# STM8S_RF433_RELAY_LEARN_CODE_V1.net
KiCad netlist of a schematic drawn in Altium Designer
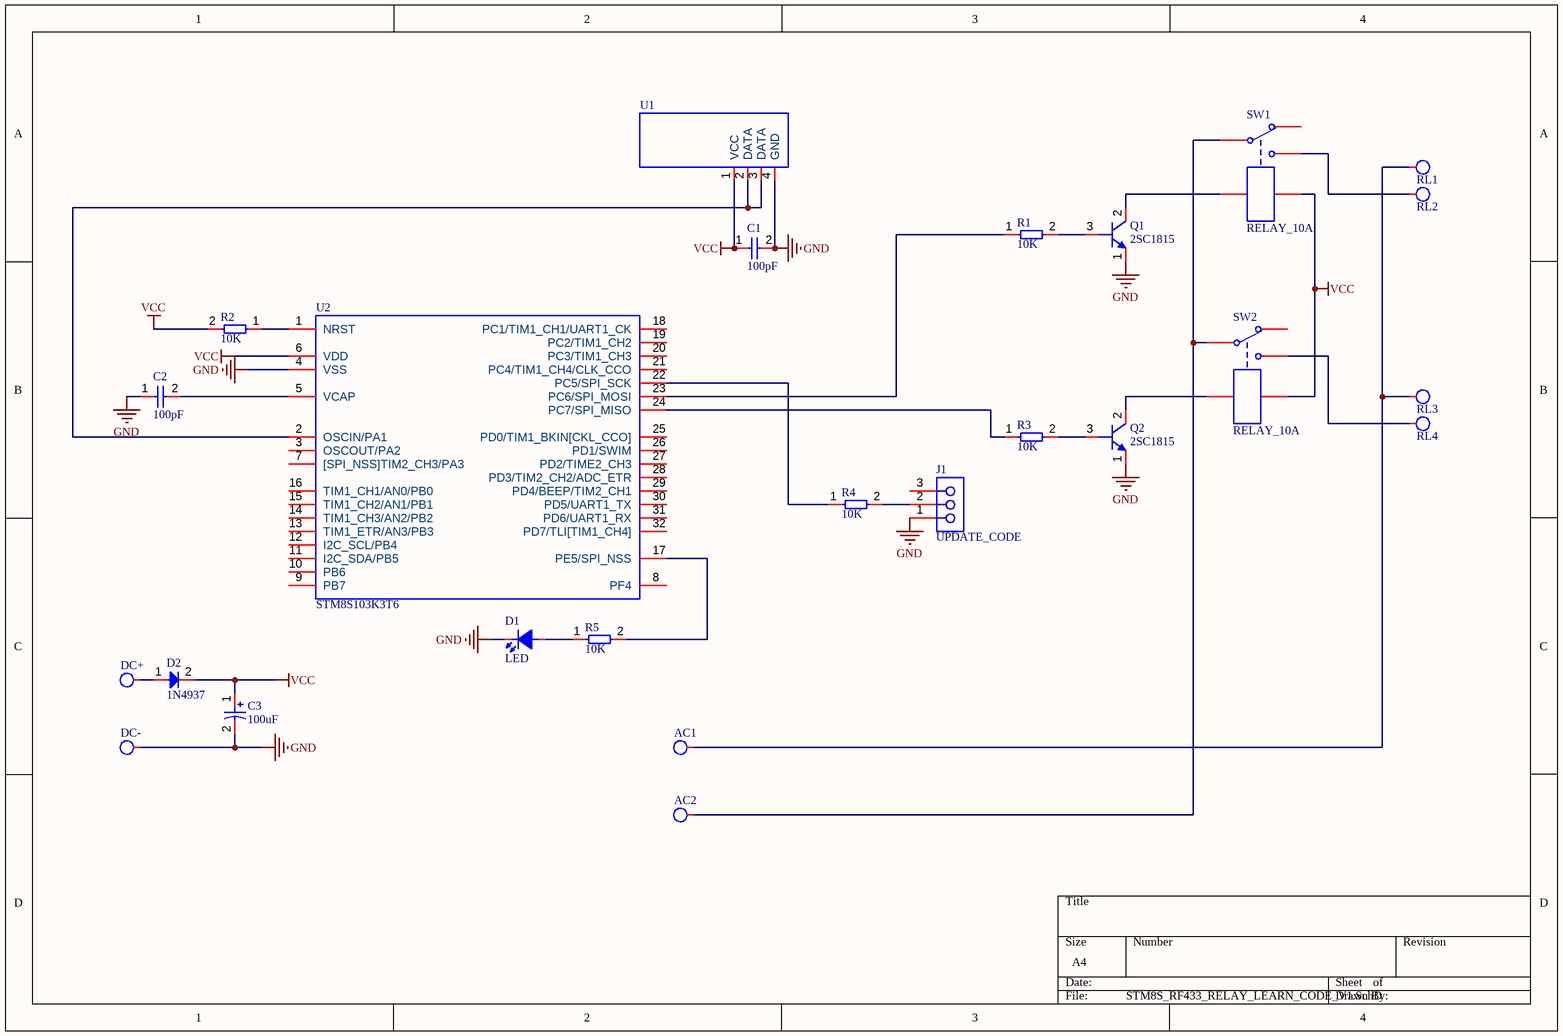
[diagram p0: STM8S_RF433_RELAY_LEARN_CODE_V1.SchDoc]

(export (version "E")
  (design (tool "Eeschema 10.0.6"))
  (components
    (comp (ref "AC1")
      (value "SolderPoint")
      (footprint "SolderPoint")
      (libsource (lib "Lib31082020") (part "SolderPoint"))
    )
    (comp (ref "AC2")
      (value "SolderPoint")
      (footprint "SolderPoint")
      (libsource (lib "Lib31082020") (part "SolderPoint"))
    )
    (comp (ref "C1")
      (value "100pF")
      (footprint "CAP_Ceramic_Disc_2")
      (libsource (lib "Lib31082020") (part "Capacitors(Disc)"))
    )
    (comp (ref "C2")
      (value "100pF")
      (footprint "CAP_Ceramic_Disc_2")
      (libsource (lib "Lib31082020") (part "Capacitors(Disc)"))
    )
    (comp (ref "C3")
      (value "100uF")
      (footprint "CAP_RAD_2.5mm")
      (libsource (lib "Lib31082020") (part "Capacitor(Radian)"))
    )
    (comp (ref "D1")
      (value "LED")
      (footprint "LED_3MM_GREEN")
      (libsource (lib "Lib31082020") (part "LED 3MM"))
    )
    (comp (ref "D2") (value "1N4937") (footprint "DO-41") (libsource (lib "Lib31082020") (part "1N4937")))
    (comp (ref "DC+")
      (value "SolderPoint")
      (footprint "SolderPoint")
      (libsource (lib "Lib31082020") (part "SolderPoint"))
    )
    (comp (ref "DC-")
      (value "SolderPoint")
      (footprint "SolderPoint")
      (libsource (lib "Lib31082020") (part "SolderPoint"))
    )
    (comp (ref "J1")
      (value "UPDATE_CODE")
      (footprint "Header 3x1 TH Pitch 2.54mm")
      (libsource (lib "Lib31082020") (part "Header 3x1 TH Pitch 2.54mm"))
    )
    (comp (ref "Q1")
      (value "2SC1815")
      (footprint "TO-92")
      (libsource (lib "Lib31082020") (part "2SC1815 (TO-92)"))
    )
    (comp (ref "Q2")
      (value "2SC1815")
      (footprint "TO-92")
      (libsource (lib "Lib31082020") (part "2SC1815 (TO-92)"))
    )
    (comp (ref "R1")
      (value "10K")
      (footprint "RES-0.25W-H-MF")
      (libsource (lib "Lib31082020") (part "Resistors THD"))
    )
    (comp (ref "R2") (value "10K") (footprint "RES-0.25W-H-MF") (libsource (lib "") (part "Resistors THD_1")))
    (comp (ref "R3")
      (value "10K")
      (footprint "RES-0.25W-H-MF")
      (libsource (lib "Lib31082020") (part "Resistors THD"))
    )
    (comp (ref "R4")
      (value "10K")
      (footprint "RES-0.25W-H-MF")
      (libsource (lib "Lib31082020") (part "Resistors THD"))
    )
    (comp (ref "R5")
      (value "10K")
      (footprint "RES-0.25W-H-MF")
      (libsource (lib "Lib31082020") (part "Resistors THD"))
    )
    (comp (ref "RL1")
      (value "AC")
      (footprint "SolderPoint")
      (libsource (lib "Lib31082020") (part "SolderPoint"))
    )
    (comp (ref "RL2")
      (value "AC")
      (footprint "SolderPoint")
      (libsource (lib "Lib31082020") (part "SolderPoint"))
    )
    (comp (ref "RL3")
      (value "AC")
      (footprint "SolderPoint")
      (libsource (lib "Lib31082020") (part "SolderPoint"))
    )
    (comp (ref "RL4")
      (value "AC")
      (footprint "SolderPoint")
      (libsource (lib "Lib31082020") (part "SolderPoint"))
    )
    (comp (ref "SW1")
      (value "RELAY_10A")
      (footprint "RELAY_10A_5PIN")
      (libsource (lib "Lib31082020") (part "RELAY_10A"))
    )
    (comp (ref "SW2")
      (value "RELAY_10A")
      (footprint "RELAY_10A_5PIN")
      (libsource (lib "Lib31082020") (part "RELAY_10A"))
    )
    (comp (ref "U1")
      (value "RF433_315_RECEVICE")
      (footprint "RF433_315_RECEVICE")
      (libsource (lib "Lib31082020") (part "RF433_315"))
    )
    (comp (ref "U2")
      (value "STM8S103K3T6")
      (footprint "LQFP032_FPT-32P-M21")
      (libsource (lib "Lib31082020") (part "STM8S103K3T6"))
    )
  )
  (nets
    (net (code "1") (name "GND") (class "Default")
      (node (ref "C1") (pin "2") (pinfunction "2_2") (pintype "passive"))
      (node (ref "C2") (pin "1") (pinfunction "1_1") (pintype "passive"))
      (node (ref "C3") (pin "2") (pinfunction "2_2") (pintype "passive"))
      (node (ref "D1") (pin "2") (pinfunction "K_2") (pintype "passive"))
      (node (ref "DC-") (pin "1") (pinfunction "1_1") (pintype "passive"))
      (node (ref "J1") (pin "1") (pinfunction "1_1") (pintype "passive"))
      (node (ref "Q1") (pin "1") (pinfunction "E_1") (pintype "passive"))
      (node (ref "Q2") (pin "1") (pinfunction "E_1") (pintype "passive"))
      (node (ref "U1") (pin "4") (pinfunction "GND_4") (pintype "passive"))
      (node (ref "U2") (pin "4") (pinfunction "VSS_4") (pintype "passive"))
    )
    (net (code "2") (name "Net-(AC1-Pad1)") (class "Default")
      (node (ref "AC1") (pin "1") (pinfunction "1_1") (pintype "passive"))
      (node (ref "RL1") (pin "1") (pinfunction "1_1") (pintype "passive"))
      (node (ref "RL3") (pin "1") (pinfunction "1_1") (pintype "passive"))
    )
    (net (code "3") (name "Net-(AC2-Pad1)") (class "Default")
      (node (ref "AC2") (pin "1") (pinfunction "1_1") (pintype "passive"))
      (node (ref "SW1") (pin "2") (pinfunction "2_2") (pintype "passive"))
      (node (ref "SW2") (pin "2") (pinfunction "2_2") (pintype "passive"))
    )
    (net (code "4") (name "Net-(D1-A)") (class "Default")
      (node (ref "D1") (pin "1") (pinfunction "A_1") (pintype "passive"))
      (node (ref "R5") (pin "1") (pinfunction "1_1") (pintype "passive"))
    )
    (net (code "5") (name "Net-(D2-Pad1)") (class "Default")
      (node (ref "D2") (pin "1") (pinfunction "1_1") (pintype "passive"))
      (node (ref "DC+") (pin "1") (pinfunction "1_1") (pintype "passive"))
    )
    (net (code "6") (name "Net-(J1-Pad2)") (class "Default")
      (node (ref "J1") (pin "2") (pinfunction "2_2") (pintype "passive"))
      (node (ref "R4") (pin "2") (pinfunction "2_2") (pintype "passive"))
    )
    (net (code "7") (name "Net-(Q1-B)") (class "Default")
      (node (ref "Q1") (pin "3") (pinfunction "B_3") (pintype "passive"))
      (node (ref "R1") (pin "2") (pinfunction "2_2") (pintype "passive"))
    )
    (net (code "8") (name "Net-(Q1-C)") (class "Default")
      (node (ref "Q1") (pin "2") (pinfunction "C_2") (pintype "passive"))
      (node (ref "SW1") (pin "1") (pinfunction "1_1") (pintype "passive"))
    )
    (net (code "9") (name "Net-(Q2-B)") (class "Default")
      (node (ref "Q2") (pin "3") (pinfunction "B_3") (pintype "passive"))
      (node (ref "R3") (pin "2") (pinfunction "2_2") (pintype "passive"))
    )
    (net (code "10") (name "Net-(Q2-C)") (class "Default")
      (node (ref "Q2") (pin "2") (pinfunction "C_2") (pintype "passive"))
      (node (ref "SW2") (pin "1") (pinfunction "1_1") (pintype "passive"))
    )
    (net (code "11") (name "Net-(RL2-Pad1)") (class "Default")
      (node (ref "RL2") (pin "1") (pinfunction "1_1") (pintype "passive"))
      (node (ref "SW1") (pin "5") (pinfunction "5_5") (pintype "passive"))
    )
    (net (code "12") (name "Net-(RL4-Pad1)") (class "Default")
      (node (ref "RL4") (pin "1") (pinfunction "1_1") (pintype "passive"))
      (node (ref "SW2") (pin "5") (pinfunction "5_5") (pintype "passive"))
    )
    (net (code "13") (name "Net-(U2-NRST)") (class "Default")
      (node (ref "R2") (pin "1") (pinfunction "1_1") (pintype "passive"))
      (node (ref "U2") (pin "1") (pinfunction "NRST_1") (pintype "passive"))
    )
    (net (code "14") (name "Net-(U2-OSCIN{slash}PA1)") (class "Default")
      (node (ref "U1") (pin "2") (pinfunction "DATA_2") (pintype "passive"))
      (node (ref "U1") (pin "3") (pinfunction "DATA_3") (pintype "passive"))
      (node (ref "U2") (pin "2") (pinfunction "OSCIN/PA1_2") (pintype "passive"))
    )
    (net (code "15") (name "Net-(U2-PC5{slash}SPI_SCK)") (class "Default")
      (node (ref "R4") (pin "1") (pinfunction "1_1") (pintype "passive"))
      (node (ref "U2") (pin "22") (pinfunction "PC5/SPI_SCK_22") (pintype "passive"))
    )
    (net (code "16") (name "Net-(U2-PC6{slash}SPI_MOSI)") (class "Default")
      (node (ref "R1") (pin "1") (pinfunction "1_1") (pintype "passive"))
      (node (ref "U2") (pin "23") (pinfunction "PC6/SPI_MOSI_23") (pintype "passive"))
    )
    (net (code "17") (name "Net-(U2-PC7{slash}SPI_MISO)") (class "Default")
      (node (ref "R3") (pin "1") (pinfunction "1_1") (pintype "passive"))
      (node (ref "U2") (pin "24") (pinfunction "PC7/SPI_MISO_24") (pintype "passive"))
    )
    (net (code "18") (name "Net-(U2-PE5{slash}SPI_NSS)") (class "Default")
      (node (ref "R5") (pin "2") (pinfunction "2_2") (pintype "passive"))
      (node (ref "U2") (pin "17") (pinfunction "PE5/SPI_NSS_17") (pintype "passive"))
    )
    (net (code "19") (name "Net-(U2-VCAP)") (class "Default")
      (node (ref "C2") (pin "2") (pinfunction "2_2") (pintype "passive"))
      (node (ref "U2") (pin "5") (pinfunction "VCAP_5") (pintype "passive"))
    )
    (net (code "20") (name "VCC") (class "Default")
      (node (ref "C1") (pin "1") (pinfunction "1_1") (pintype "passive"))
      (node (ref "C3") (pin "1") (pinfunction "1_1") (pintype "passive"))
      (node (ref "D2") (pin "2") (pinfunction "2_2") (pintype "passive"))
      (node (ref "R2") (pin "2") (pinfunction "2_2") (pintype "passive"))
      (node (ref "SW1") (pin "3") (pinfunction "3_3") (pintype "passive"))
      (node (ref "SW2") (pin "3") (pinfunction "3_3") (pintype "passive"))
      (node (ref "U1") (pin "1") (pinfunction "VCC_1") (pintype "passive"))
      (node (ref "U2") (pin "6") (pinfunction "VDD_6") (pintype "passive"))
    )
    (net (code "21") (name "unconnected-(J1-Pad3)") (class "Default")
      (node (ref "J1") (pin "3") (pinfunction "3_3") (pintype "passive"))
    )
    (net (code "22") (name "unconnected-(SW1-Pad4)") (class "Default")
      (node (ref "SW1") (pin "4") (pinfunction "4_4") (pintype "passive"))
    )
    (net (code "23") (name "unconnected-(SW2-Pad4)") (class "Default")
      (node (ref "SW2") (pin "4") (pinfunction "4_4") (pintype "passive"))
    )
    (net (code "24") (name "unconnected-(U2-I2C_SCL{slash}PB4-Pad12)") (class "Default")
      (node (ref "U2") (pin "12") (pinfunction "I2C_SCL/PB4_12") (pintype "passive"))
    )
    (net (code "25") (name "unconnected-(U2-I2C_SDA{slash}PB5-Pad11)") (class "Default")
      (node (ref "U2") (pin "11") (pinfunction "I2C_SDA/PB5_11") (pintype "passive"))
    )
    (net (code "26") (name "unconnected-(U2-OSCOUT{slash}PA2-Pad3)") (class "Default")
      (node (ref "U2") (pin "3") (pinfunction "OSCOUT/PA2_3") (pintype "passive"))
    )
    (net (code "27") (name "unconnected-(U2-PB6-Pad10)") (class "Default")
      (node (ref "U2") (pin "10") (pinfunction "PB6_10") (pintype "passive"))
    )
    (net (code "28") (name "unconnected-(U2-PB7-Pad9)") (class "Default")
      (node (ref "U2") (pin "9") (pinfunction "PB7_9") (pintype "passive"))
    )
    (net (code "29") (name "unconnected-(U2-PC1{slash}TIM1_CH1{slash}UART1_CK-Pad18)") (class "Default")
      (node (ref "U2") (pin "18") (pinfunction "PC1/TIM1_CH1/UART1_CK_18") (pintype "passive"))
    )
    (net (code "30") (name "unconnected-(U2-PC2{slash}TIM1_CH2-Pad19)") (class "Default")
      (node (ref "U2") (pin "19") (pinfunction "PC2/TIM1_CH2_19") (pintype "passive"))
    )
    (net (code "31") (name "unconnected-(U2-PC3{slash}TIM1_CH3-Pad20)") (class "Default")
      (node (ref "U2") (pin "20") (pinfunction "PC3/TIM1_CH3_20") (pintype "passive"))
    )
    (net (code "32") (name "unconnected-(U2-PC4{slash}TIM1_CH4{slash}CLK_CCO-Pad21)") (class "Default")
      (node (ref "U2") (pin "21") (pinfunction "PC4/TIM1_CH4/CLK_CCO_21") (pintype "passive"))
    )
    (net (code "33") (name "unconnected-(U2-PD0{slash}TIM1_BKIN[CKL_CCO]-Pad25)") (class "Default")
      (node (ref "U2") (pin "25") (pinfunction "PD0/TIM1_BKIN[CKL_CCO]_25") (pintype "passive"))
    )
    (net (code "34") (name "unconnected-(U2-PD1{slash}SWIM-Pad26)") (class "Default")
      (node (ref "U2") (pin "26") (pinfunction "PD1/SWIM_26") (pintype "passive"))
    )
    (net (code "35") (name "unconnected-(U2-PD2{slash}TIME2_CH3-Pad27)") (class "Default")
      (node (ref "U2") (pin "27") (pinfunction "PD2/TIME2_CH3_27") (pintype "passive"))
    )
    (net (code "36") (name "unconnected-(U2-PD3{slash}TIM2_CH2{slash}ADC_ETR-Pad28)") (class "Default")
      (node (ref "U2") (pin "28") (pinfunction "PD3/TIM2_CH2/ADC_ETR_28") (pintype "passive"))
    )
    (net (code "37") (name "unconnected-(U2-PD4{slash}BEEP{slash}TIM2_CH1-Pad29)") (class "Default")
      (node (ref "U2") (pin "29") (pinfunction "PD4/BEEP/TIM2_CH1_29") (pintype "passive"))
    )
    (net (code "38") (name "unconnected-(U2-PD5{slash}UART1_TX-Pad30)") (class "Default")
      (node (ref "U2") (pin "30") (pinfunction "PD5/UART1_TX_30") (pintype "passive"))
    )
    (net (code "39") (name "unconnected-(U2-PD6{slash}UART1_RX-Pad31)") (class "Default")
      (node (ref "U2") (pin "31") (pinfunction "PD6/UART1_RX_31") (pintype "passive"))
    )
    (net (code "40") (name "unconnected-(U2-PD7{slash}TLI[TIM1_CH4]-Pad32)") (class "Default")
      (node (ref "U2") (pin "32") (pinfunction "PD7/TLI[TIM1_CH4]_32") (pintype "passive"))
    )
    (net (code "41") (name "unconnected-(U2-PF4-Pad8)") (class "Default")
      (node (ref "U2") (pin "8") (pinfunction "PF4_8") (pintype "passive"))
    )
    (net (code "42") (name "unconnected-(U2-TIM1_CH1{slash}AN0{slash}PB0-Pad16)") (class "Default")
      (node (ref "U2") (pin "16") (pinfunction "TIM1_CH1/AN0/PB0_16") (pintype "passive"))
    )
    (net (code "43") (name "unconnected-(U2-TIM1_CH2{slash}AN1{slash}PB1-Pad15)") (class "Default")
      (node (ref "U2") (pin "15") (pinfunction "TIM1_CH2/AN1/PB1_15") (pintype "passive"))
    )
    (net (code "44") (name "unconnected-(U2-TIM1_CH3{slash}AN2{slash}PB2-Pad14)") (class "Default")
      (node (ref "U2") (pin "14") (pinfunction "TIM1_CH3/AN2/PB2_14") (pintype "passive"))
    )
    (net (code "45") (name "unconnected-(U2-TIM1_ETR{slash}AN3{slash}PB3-Pad13)") (class "Default")
      (node (ref "U2") (pin "13") (pinfunction "TIM1_ETR/AN3/PB3_13") (pintype "passive"))
    )
    (net (code "46") (name "unconnected-(U2-[SPI_NSS]TIM2_CH3{slash}PA3-Pad7)") (class "Default")
      (node (ref "U2") (pin "7") (pinfunction "[SPI_NSS]TIM2_CH3/PA3_7") (pintype "passive"))
    )
  )
)
